# irblueV_2.net
KiCad netlist of a schematic drawn in EAGLE
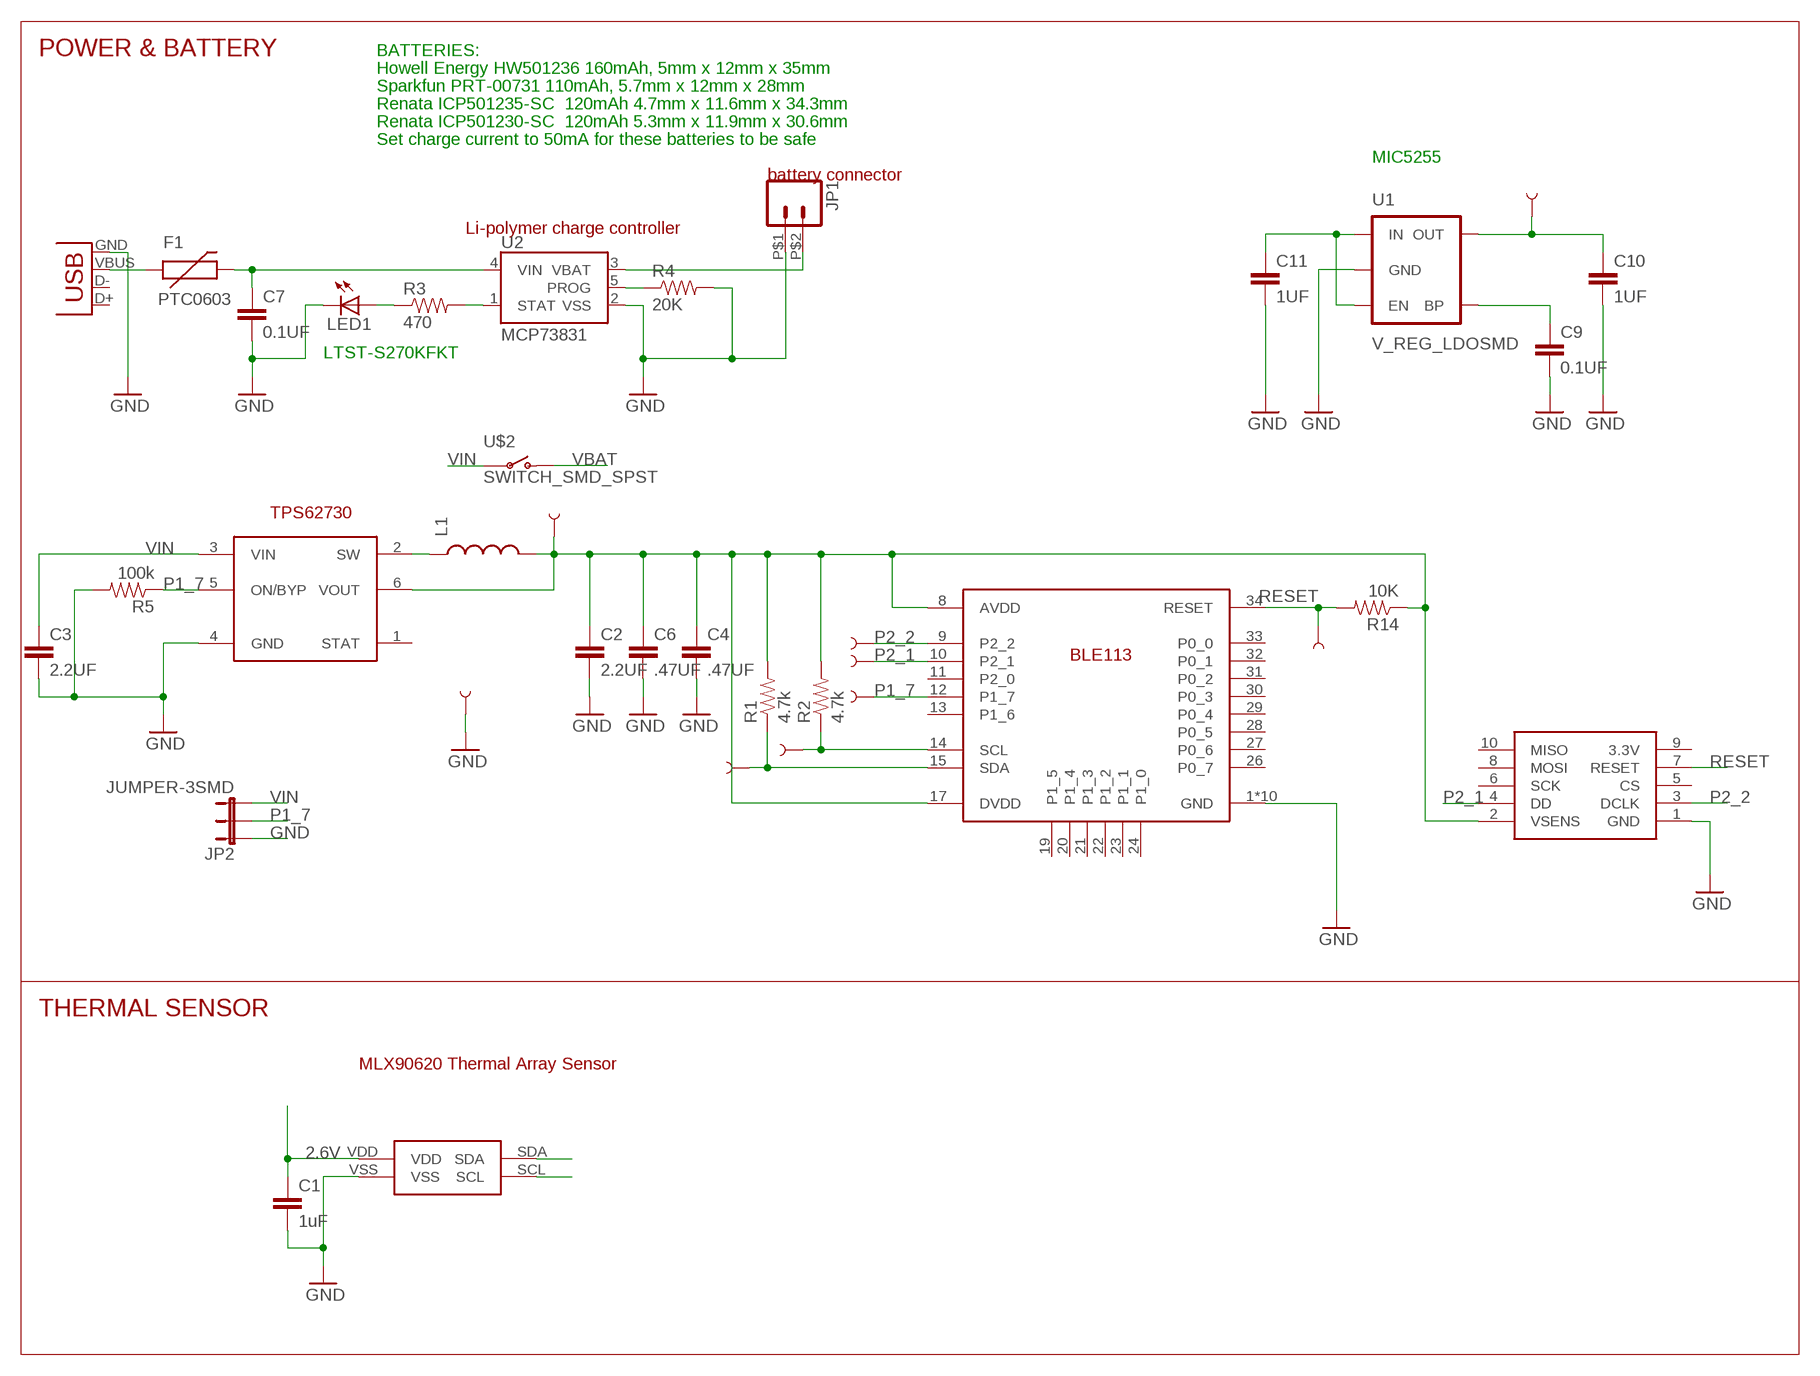
[diagram p0: schematic, sheet 1]

(export (version "E")
  (design (tool "Eeschema 10.0.6"))
  (components
    (comp (ref "C1")
      (value "1uF")
      (footprint "eagle-import:0402-CAP")
      (libsource (lib "eagle-import") (part "CAP0402-CAP"))
    )
    (comp (ref "C2")
      (value "2.2UF")
      (footprint "eagle-import:0603-CAP")
      (libsource (lib "eagle-import") (part "CAP0603-CAP"))
    )
    (comp (ref "C3")
      (value "2.2UF")
      (footprint "eagle-import:0603-CAP")
      (libsource (lib "eagle-import") (part "CAP0603-CAP"))
    )
    (comp (ref "C4")
      (value ".47UF")
      (footprint "eagle-import:0402-CAP")
      (libsource (lib "eagle-import") (part "CAP0402-CAP"))
    )
    (comp (ref "C6")
      (value ".47UF")
      (footprint "eagle-import:0402-CAP")
      (libsource (lib "eagle-import") (part "CAP0402-CAP"))
    )
    (comp (ref "C7")
      (value "0.1UF")
      (footprint "eagle-import:0402-CAP")
      (libsource (lib "eagle-import") (part "11.ee_projects_CAP0402-CAP"))
    )
    (comp (ref "C9")
      (value "0.1UF")
      (footprint "eagle-import:0402-CAP")
      (libsource (lib "eagle-import") (part "11.ee_projects_CAP0402-CAP"))
    )
    (comp (ref "C10")
      (value "1UF")
      (footprint "eagle-import:0402-CAP")
      (libsource (lib "eagle-import") (part "11.ee_projects_CAP0402-CAP"))
    )
    (comp (ref "C11")
      (value "1UF")
      (footprint "eagle-import:0402-CAP")
      (libsource (lib "eagle-import") (part "11.ee_projects_CAP0402-CAP"))
    )
    (comp (ref "F1")
      (value "PTC0603")
      (footprint "eagle-import:0603")
      (libsource (lib "eagle-import") (part "PTC0603"))
    )
    (comp (ref "JP1")
      (value "M02WIRE")
      (footprint "eagle-import:1X02_1-WIRE")
      (libsource (lib "eagle-import") (part "M02WIRE"))
    )
    (comp (ref "JP2")
      (value "JUMPER-3SMD")
      (footprint "eagle-import:SJ_3")
      (libsource (lib "eagle-import") (part "JUMPER-3SMD"))
    )
    (comp (ref "L1")
      (value "INDUCTOR0805")
      (footprint "eagle-import:0805")
      (libsource (lib "eagle-import") (part "INDUCTOR0805"))
    )
    (comp (ref "LED1")
      (value "LED0603")
      (footprint "eagle-import:LED-0603")
      (libsource (lib "eagle-import") (part "LED0603"))
    )
    (comp (ref "R1")
      (value "4.7k")
      (footprint "eagle-import:0402-RES")
      (libsource (lib "eagle-import") (part "RESISTOR0402-RES"))
    )
    (comp (ref "R2")
      (value "4.7k")
      (footprint "eagle-import:0402-RES")
      (libsource (lib "eagle-import") (part "RESISTOR0402-RES"))
    )
    (comp (ref "R3")
      (value "470")
      (footprint "eagle-import:0402-RES")
      (libsource (lib "eagle-import") (part "11.ee_projects_RESISTOR0402-RES"))
    )
    (comp (ref "R4")
      (value "20K")
      (footprint "eagle-import:0402-RES")
      (libsource (lib "eagle-import") (part "11.ee_projects_RESISTOR0402-RES"))
    )
    (comp (ref "R5")
      (value "100k")
      (footprint "eagle-import:0402-RES")
      (libsource (lib "eagle-import") (part "RESISTOR0402-RES"))
    )
    (comp (ref "R14")
      (value "10K")
      (footprint "eagle-import:0402-RES")
      (libsource (lib "eagle-import") (part "RESISTOR0402-RES"))
    )
    (comp (ref "S1")
      (value "MLX90620")
      (footprint "eagle-import:MLX90620")
      (libsource (lib "eagle-import") (part "MLX90620"))
    )
    (comp (ref "TP1")
      (value "TEST-POINT3X5")
      (footprint "eagle-import:PAD.03X.05")
      (libsource (lib "eagle-import") (part "TEST-POINT3X5"))
    )
    (comp (ref "TP2")
      (value "TEST-POINT3X5")
      (footprint "eagle-import:PAD.03X.05")
      (libsource (lib "eagle-import") (part "TEST-POINT3X5"))
    )
    (comp (ref "TP3")
      (value "TEST-POINT3X5")
      (footprint "eagle-import:PAD.03X.05")
      (libsource (lib "eagle-import") (part "TEST-POINT3X5"))
    )
    (comp (ref "TP4")
      (value "TEST-POINT3X5")
      (footprint "eagle-import:PAD.03X.05")
      (libsource (lib "eagle-import") (part "TEST-POINT3X5"))
    )
    (comp (ref "TP5")
      (value "TEST-POINT3X5")
      (footprint "eagle-import:PAD.03X.05")
      (libsource (lib "eagle-import") (part "TEST-POINT3X5"))
    )
    (comp (ref "TP6")
      (value "TEST-POINT3X5")
      (footprint "eagle-import:PAD.03X.05")
      (libsource (lib "eagle-import") (part "TEST-POINT3X5"))
    )
    (comp (ref "TP7")
      (value "TEST-POINT3X5")
      (footprint "eagle-import:PAD.03X.05")
      (libsource (lib "eagle-import") (part "TEST-POINT3X5"))
    )
    (comp (ref "TP8")
      (value "TEST-POINT3X5")
      (footprint "eagle-import:PAD.03X.05")
      (libsource (lib "eagle-import") (part "TEST-POINT3X5"))
    )
    (comp (ref "TP9")
      (value "TEST-POINT3X5")
      (footprint "eagle-import:PAD.03X.05")
      (libsource (lib "eagle-import") (part "TEST-POINT3X5"))
    )
    (comp (ref "U$1")
      (value "TPS62730")
      (footprint "eagle-import:SON-6")
      (libsource (lib "eagle-import") (part "TPS62730"))
    )
    (comp (ref "U$2")
      (value "SWITCH_SMD_SPST")
      (footprint "eagle-import:SWITCH-SPDT-SMD")
      (fields (field (name "MFG") "C&K Components"))
      (libsource (lib "eagle-import") (part "SWITCH_SMD_SPST"))
    )
    (comp (ref "U$5")
      (value "BLE113")
      (footprint "eagle-import:BLE113")
      (libsource (lib "eagle-import") (part "BLE113"))
    )
    (comp (ref "U$8")
      (value "TAG_CONNECT_CC_DEBUGGER")
      (footprint "eagle-import:TC2030-MCP-NL")
      (libsource (lib "eagle-import") (part "TAG_CONNECT_CC_DEBUGGER"))
    )
    (comp (ref "U1")
      (value "V_REG_LDOSMD")
      (footprint "eagle-import:SOT23-5")
      (libsource (lib "eagle-import") (part "V_REG_LDOSMD"))
    )
    (comp (ref "U2")
      (value "MCP73831")
      (footprint "eagle-import:SOT23-5")
      (libsource (lib "eagle-import") (part "MCP73831"))
    )
    (comp (ref "X1")
      (value "USB-MICROB")
      (footprint "eagle-import:USB-MICROB")
      (libsource (lib "eagle-import") (part "USB-MICROB"))
    )
  )
  (nets
    (net (code "1") (name "/2.6V") (class "Default")
      (node (ref "C1") (pin "1") (pinfunction "1_1") (pintype "passive"))
      (node (ref "C10") (pin "1") (pinfunction "1_1") (pintype "passive"))
      (node (ref "S1") (pin "VDD") (pinfunction "VDD_VDD") (pintype "bidirectional"))
      (node (ref "TP9") (pin "P$1") (pinfunction "1_P$1") (pintype "bidirectional"))
      (node (ref "U1") (pin "5") (pinfunction "OUT_5") (pintype "passive"))
    )
    (net (code "2") (name "/P1_7") (class "Default")
      (node (ref "JP2") (pin "2") (pinfunction "2_2") (pintype "passive"))
      (node (ref "R5") (pin "1") (pinfunction "1_1") (pintype "passive"))
      (node (ref "TP3") (pin "P$1") (pinfunction "1_P$1") (pintype "bidirectional"))
      (node (ref "U$1") (pin "5") (pinfunction "ON/BYP_5") (pintype "bidirectional"))
      (node (ref "U$5") (pin "12") (pinfunction "P1_7_12") (pintype "bidirectional"))
    )
    (net (code "3") (name "/P2_1") (class "Default")
      (node (ref "TP2") (pin "P$1") (pinfunction "1_P$1") (pintype "bidirectional"))
      (node (ref "U$5") (pin "10") (pinfunction "P2_1_10") (pintype "bidirectional"))
      (node (ref "U$8") (pin "4") (pinfunction "DD_4") (pintype "bidirectional"))
    )
    (net (code "4") (name "/P2_2") (class "Default")
      (node (ref "TP1") (pin "P$1") (pinfunction "1_P$1") (pintype "bidirectional"))
      (node (ref "U$5") (pin "9") (pinfunction "P2_2_9") (pintype "bidirectional"))
      (node (ref "U$8") (pin "3") (pinfunction "DCLK_3") (pintype "bidirectional"))
    )
    (net (code "5") (name "/RESET") (class "Default")
      (node (ref "R14") (pin "2") (pinfunction "2_2") (pintype "passive"))
      (node (ref "TP4") (pin "P$1") (pinfunction "1_P$1") (pintype "bidirectional"))
      (node (ref "U$5") (pin "34") (pinfunction "RESET_34") (pintype "bidirectional"))
      (node (ref "U$8") (pin "7") (pinfunction "RESET_7") (pintype "bidirectional"))
    )
    (net (code "6") (name "/SCL") (class "Default")
      (node (ref "R2") (pin "1") (pinfunction "1_1") (pintype "passive"))
      (node (ref "S1") (pin "SCL") (pinfunction "SCL_SCL") (pintype "bidirectional"))
      (node (ref "TP5") (pin "P$1") (pinfunction "1_P$1") (pintype "bidirectional"))
      (node (ref "U$5") (pin "14") (pinfunction "SCL_14") (pintype "bidirectional"))
    )
    (net (code "7") (name "/SDA") (class "Default")
      (node (ref "R1") (pin "1") (pinfunction "1_1") (pintype "passive"))
      (node (ref "S1") (pin "SDA") (pinfunction "SDA_SDA") (pintype "bidirectional"))
      (node (ref "TP6") (pin "P$1") (pinfunction "1_P$1") (pintype "bidirectional"))
      (node (ref "U$5") (pin "15") (pinfunction "SDA_15") (pintype "bidirectional"))
    )
    (net (code "8") (name "/VBAT") (class "Default")
      (node (ref "JP1") (pin "P$2") (pinfunction "2_P$2") (pintype "passive"))
      (node (ref "U$2") (pin "1") (pinfunction "O_1") (pintype "passive"))
      (node (ref "U2") (pin "3") (pinfunction "VBAT_3") (pintype "power_in"))
    )
    (net (code "9") (name "/VIN") (class "Default")
      (node (ref "C11") (pin "1") (pinfunction "1_1") (pintype "passive"))
      (node (ref "C3") (pin "1") (pinfunction "1_1") (pintype "passive"))
      (node (ref "JP2") (pin "3") (pinfunction "3_3") (pintype "passive"))
      (node (ref "U$1") (pin "3") (pinfunction "VIN_3") (pintype "bidirectional"))
      (node (ref "U$2") (pin "2") (pinfunction "P_2") (pintype "passive"))
      (node (ref "U1") (pin "1") (pinfunction "IN_1") (pintype "input"))
      (node (ref "U1") (pin "3") (pinfunction "EN_3") (pintype "input"))
    )
    (net (code "10") (name "GND") (class "Default")
      (node (ref "C1") (pin "2") (pinfunction "2_2") (pintype "passive"))
      (node (ref "C10") (pin "2") (pinfunction "2_2") (pintype "passive"))
      (node (ref "C11") (pin "2") (pinfunction "2_2") (pintype "passive"))
      (node (ref "C2") (pin "2") (pinfunction "2_2") (pintype "passive"))
      (node (ref "C3") (pin "2") (pinfunction "2_2") (pintype "passive"))
      (node (ref "C4") (pin "2") (pinfunction "2_2") (pintype "passive"))
      (node (ref "C6") (pin "2") (pinfunction "2_2") (pintype "passive"))
      (node (ref "C7") (pin "2") (pinfunction "2_2") (pintype "passive"))
      (node (ref "C9") (pin "2") (pinfunction "2_2") (pintype "passive"))
      (node (ref "JP1") (pin "P$1") (pinfunction "1_P$1") (pintype "passive"))
      (node (ref "JP2") (pin "1") (pinfunction "1_1") (pintype "passive"))
      (node (ref "LED1") (pin "C") (pinfunction "C_C") (pintype "passive"))
      (node (ref "R4") (pin "2") (pinfunction "2_2") (pintype "passive"))
      (node (ref "R5") (pin "2") (pinfunction "2_2") (pintype "passive"))
      (node (ref "S1") (pin "VSS") (pinfunction "VSS_VSS") (pintype "bidirectional"))
      (node (ref "TP8") (pin "P$1") (pinfunction "1_P$1") (pintype "bidirectional"))
      (node (ref "U$1") (pin "4") (pinfunction "GND_4") (pintype "bidirectional"))
      (node (ref "U$5") (pin "1") (pinfunction "GND_1") (pintype "bidirectional"))
      (node (ref "U$5") (pin "18") (pinfunction "GND_18") (pintype "bidirectional"))
      (node (ref "U$5") (pin "2") (pinfunction "GND_2") (pintype "bidirectional"))
      (node (ref "U$5") (pin "25") (pinfunction "GND_25") (pintype "bidirectional"))
      (node (ref "U$5") (pin "3") (pinfunction "GND_3") (pintype "bidirectional"))
      (node (ref "U$5") (pin "36") (pinfunction "GND_36") (pintype "bidirectional"))
      (node (ref "U$5") (pin "4") (pinfunction "GND_4") (pintype "bidirectional"))
      (node (ref "U$5") (pin "5") (pinfunction "GND_5") (pintype "bidirectional"))
      (node (ref "U$5") (pin "6") (pinfunction "GND_6") (pintype "bidirectional"))
      (node (ref "U$5") (pin "7") (pinfunction "GND_7") (pintype "bidirectional"))
      (node (ref "U$8") (pin "1") (pinfunction "GND_1") (pintype "bidirectional"))
      (node (ref "U1") (pin "2") (pinfunction "GND_2") (pintype "input"))
      (node (ref "U2") (pin "2") (pinfunction "VSS_2") (pintype "power_in"))
      (node (ref "X1") (pin "GND") (pinfunction "GND_GND") (pintype "bidirectional"))
    )
    (net (code "11") (name "Net-(F1-Pad1)") (class "Default")
      (node (ref "F1") (pin "1") (pinfunction "1_1") (pintype "bidirectional"))
      (node (ref "X1") (pin "VBUS") (pinfunction "VBUS_VBUS") (pintype "bidirectional"))
    )
    (net (code "12") (name "Net-(LED1-PadA)") (class "Default")
      (node (ref "LED1") (pin "A") (pinfunction "A_A") (pintype "passive"))
      (node (ref "R3") (pin "1") (pinfunction "1_1") (pintype "passive"))
    )
    (net (code "13") (name "Net-(TP7-1)") (class "Default")
      (node (ref "C2") (pin "1") (pinfunction "1_1") (pintype "passive"))
      (node (ref "C4") (pin "1") (pinfunction "1_1") (pintype "passive"))
      (node (ref "C6") (pin "1") (pinfunction "1_1") (pintype "passive"))
      (node (ref "L1") (pin "2") (pinfunction "2_2") (pintype "passive"))
      (node (ref "R1") (pin "2") (pinfunction "2_2") (pintype "passive"))
      (node (ref "R14") (pin "1") (pinfunction "1_1") (pintype "passive"))
      (node (ref "R2") (pin "2") (pinfunction "2_2") (pintype "passive"))
      (node (ref "TP7") (pin "P$1") (pinfunction "1_P$1") (pintype "bidirectional"))
      (node (ref "U$1") (pin "6") (pinfunction "VOUT_6") (pintype "bidirectional"))
      (node (ref "U$5") (pin "17") (pinfunction "DVDD_17") (pintype "bidirectional"))
      (node (ref "U$5") (pin "8") (pinfunction "AVDD_8") (pintype "bidirectional"))
      (node (ref "U$8") (pin "2") (pinfunction "VSENS_2") (pintype "bidirectional"))
    )
    (net (code "14") (name "Net-(U$1-SW)") (class "Default")
      (node (ref "L1") (pin "1") (pinfunction "1_1") (pintype "passive"))
      (node (ref "U$1") (pin "2") (pinfunction "SW_2") (pintype "bidirectional"))
    )
    (net (code "15") (name "Net-(U1-BP)") (class "Default")
      (node (ref "C9") (pin "1") (pinfunction "1_1") (pintype "passive"))
      (node (ref "U1") (pin "4") (pinfunction "BP_4") (pintype "input"))
    )
    (net (code "16") (name "Net-(U2-PROG)") (class "Default")
      (node (ref "R4") (pin "1") (pinfunction "1_1") (pintype "passive"))
      (node (ref "U2") (pin "5") (pinfunction "PROG_5") (pintype "input"))
    )
    (net (code "17") (name "Net-(U2-STAT)") (class "Default")
      (node (ref "R3") (pin "2") (pinfunction "2_2") (pintype "passive"))
      (node (ref "U2") (pin "1") (pinfunction "STAT_1") (pintype "output"))
    )
    (net (code "18") (name "Net-(U2-VIN)") (class "Default")
      (node (ref "C7") (pin "1") (pinfunction "1_1") (pintype "passive"))
      (node (ref "F1") (pin "2") (pinfunction "2_2") (pintype "bidirectional"))
      (node (ref "U2") (pin "4") (pinfunction "VIN_4") (pintype "power_in"))
    )
    (net (code "19") (name "unconnected-(U$1-STAT-Pad1)") (class "Default")
      (node (ref "U$1") (pin "1") (pinfunction "STAT_1") (pintype "bidirectional"))
    )
    (net (code "20") (name "unconnected-(U$5-P0_0-Pad33)") (class "Default")
      (node (ref "U$5") (pin "33") (pinfunction "P0_0_33") (pintype "bidirectional"))
    )
    (net (code "21") (name "unconnected-(U$5-P0_1-Pad32)") (class "Default")
      (node (ref "U$5") (pin "32") (pinfunction "P0_1_32") (pintype "bidirectional"))
    )
    (net (code "22") (name "unconnected-(U$5-P0_2-Pad31)") (class "Default")
      (node (ref "U$5") (pin "31") (pinfunction "P0_2_31") (pintype "bidirectional"))
    )
    (net (code "23") (name "unconnected-(U$5-P0_3-Pad30)") (class "Default")
      (node (ref "U$5") (pin "30") (pinfunction "P0_3_30") (pintype "bidirectional"))
    )
    (net (code "24") (name "unconnected-(U$5-P0_4-Pad29)") (class "Default")
      (node (ref "U$5") (pin "29") (pinfunction "P0_4_29") (pintype "bidirectional"))
    )
    (net (code "25") (name "unconnected-(U$5-P0_5-Pad28)") (class "Default")
      (node (ref "U$5") (pin "28") (pinfunction "P0_5_28") (pintype "bidirectional"))
    )
    (net (code "26") (name "unconnected-(U$5-P0_6-Pad27)") (class "Default")
      (node (ref "U$5") (pin "27") (pinfunction "P0_6_27") (pintype "bidirectional"))
    )
    (net (code "27") (name "unconnected-(U$5-P0_7-Pad26)") (class "Default")
      (node (ref "U$5") (pin "26") (pinfunction "P0_7_26") (pintype "bidirectional"))
    )
    (net (code "28") (name "unconnected-(U$5-P1_0-Pad24)") (class "Default")
      (node (ref "U$5") (pin "24") (pinfunction "P1_0_24") (pintype "bidirectional"))
    )
    (net (code "29") (name "unconnected-(U$5-P1_1-Pad23)") (class "Default")
      (node (ref "U$5") (pin "23") (pinfunction "P1_1_23") (pintype "bidirectional"))
    )
    (net (code "30") (name "unconnected-(U$5-P1_2-Pad22)") (class "Default")
      (node (ref "U$5") (pin "22") (pinfunction "P1_2_22") (pintype "bidirectional"))
    )
    (net (code "31") (name "unconnected-(U$5-P1_3-Pad21)") (class "Default")
      (node (ref "U$5") (pin "21") (pinfunction "P1_3_21") (pintype "bidirectional"))
    )
    (net (code "32") (name "unconnected-(U$5-P1_4-Pad20)") (class "Default")
      (node (ref "U$5") (pin "20") (pinfunction "P1_4_20") (pintype "bidirectional"))
    )
    (net (code "33") (name "unconnected-(U$5-P1_5-Pad19)") (class "Default")
      (node (ref "U$5") (pin "19") (pinfunction "P1_5_19") (pintype "bidirectional"))
    )
    (net (code "34") (name "unconnected-(U$5-P1_6-Pad13)") (class "Default")
      (node (ref "U$5") (pin "13") (pinfunction "P1_6_13") (pintype "bidirectional"))
    )
    (net (code "35") (name "unconnected-(U$5-P2_0-Pad11)") (class "Default")
      (node (ref "U$5") (pin "11") (pinfunction "P2_0_11") (pintype "bidirectional"))
    )
    (net (code "36") (name "unconnected-(U$8-3.3V-Pad9)") (class "Default")
      (node (ref "U$8") (pin "9") (pinfunction "3.3V_9") (pintype "bidirectional"))
    )
    (net (code "37") (name "unconnected-(U$8-CS-Pad5)") (class "Default")
      (node (ref "U$8") (pin "5") (pinfunction "CS_5") (pintype "bidirectional"))
    )
    (net (code "38") (name "unconnected-(U$8-MISO-Pad10)") (class "Default")
      (node (ref "U$8") (pin "10") (pinfunction "MISO_10") (pintype "bidirectional"))
    )
    (net (code "39") (name "unconnected-(U$8-MOSI-Pad8)") (class "Default")
      (node (ref "U$8") (pin "8") (pinfunction "MOSI_8") (pintype "bidirectional"))
    )
    (net (code "40") (name "unconnected-(U$8-SCK-Pad6)") (class "Default")
      (node (ref "U$8") (pin "6") (pinfunction "SCK_6") (pintype "bidirectional"))
    )
    (net (code "41") (name "unconnected-(X1-PadD+)") (class "Default")
      (node (ref "X1") (pin "D+") (pinfunction "D+_D+") (pintype "bidirectional"))
    )
    (net (code "42") (name "unconnected-(X1-PadD-)") (class "Default")
      (node (ref "X1") (pin "D-") (pinfunction "D-_D-") (pintype "bidirectional"))
    )
  )
)
